# CAN.net
KiCad netlist of a schematic drawn in Altium Designer
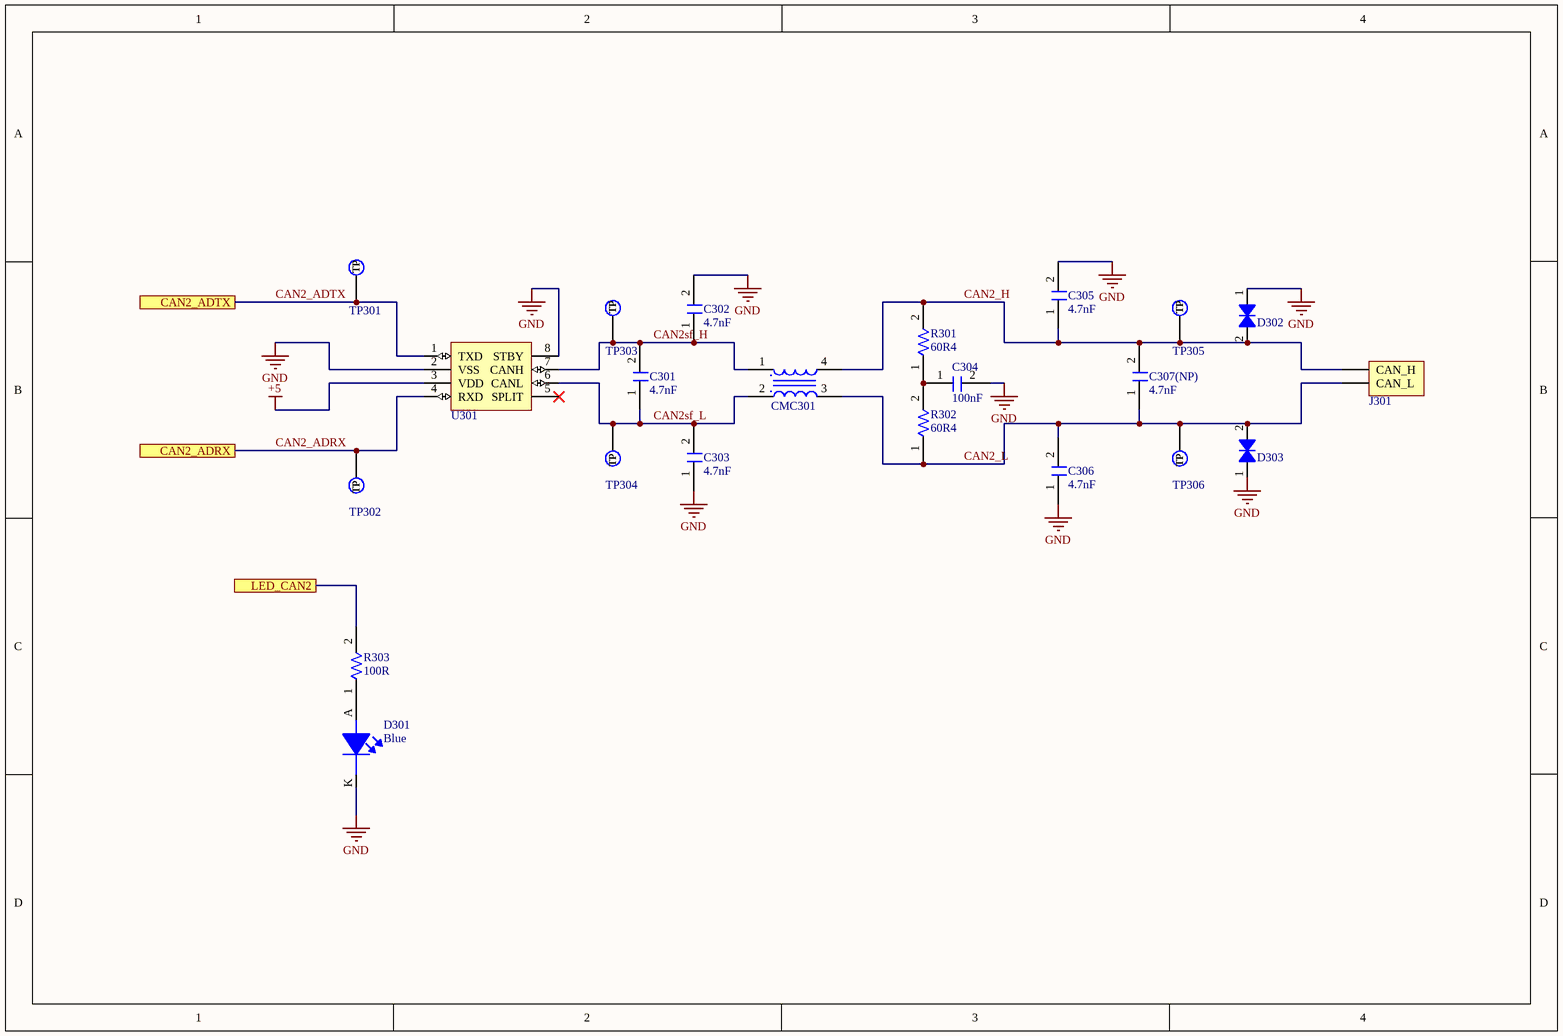
[diagram p0: CAN.SchDoc]

(export (version "E")
  (design (tool "Eeschema 10.0.6"))
  (components
    (comp (ref "C301")
      (value "885012208025")
      (footprint "C1206FNPC-RW")
      (description "Cap, 4700PF, 16V, 10%, X7R, 1206")
      (fields
        (field (name "MANUFACTURER") "Wurth Electronics")
        (field (name "TOLERANCE") "10%")
        (field (name "CAPACITANCE") "4.7nF")
      )
      (libsource (lib "Passives") (part "C4.7n-16V-1206FNPC-X7R"))
    )
    (comp (ref "C302")
      (value "885012208025")
      (footprint "C1206FNPC-RW")
      (description "Cap, 4700PF, 16V, 10%, X7R, 1206")
      (fields
        (field (name "MANUFACTURER") "Wurth Electronics")
        (field (name "TOLERANCE") "10%")
        (field (name "CAPACITANCE") "4.7nF")
      )
      (libsource (lib "Passives") (part "C4.7n-16V-1206FNPC-X7R"))
    )
    (comp (ref "C303")
      (value "885012208025")
      (footprint "C1206FNPC-RW")
      (description "Cap, 4700PF, 16V, 10%, X7R, 1206")
      (fields
        (field (name "MANUFACTURER") "Wurth Electronics")
        (field (name "TOLERANCE") "10%")
        (field (name "CAPACITANCE") "4.7nF")
      )
      (libsource (lib "Passives") (part "C4.7n-16V-1206FNPC-X7R"))
    )
    (comp (ref "C304")
      (value "885012208009")
      (footprint "C1206FNPC-RW")
      (description "Cap, 0.1ΜF, 10V, 10%, X7R, 1206")
      (fields (field (name "TOLERANCE") "10%") (field (name "CAPACITANCE") "100nF"))
      (libsource (lib "Passives") (part "C100n-10V-1206FNPC-X7R"))
    )
    (comp (ref "C305")
      (value "885012208025")
      (footprint "C1206FNPC-RW")
      (description "Cap, 4700PF, 16V, 10%, X7R, 1206")
      (fields
        (field (name "MANUFACTURER") "Wurth Electronics")
        (field (name "TOLERANCE") "10%")
        (field (name "CAPACITANCE") "4.7nF")
      )
      (libsource (lib "Passives") (part "C4.7n-16V-1206FNPC-X7R"))
    )
    (comp (ref "C306")
      (value "885012208025")
      (footprint "C1206FNPC-RW")
      (description "Cap, 4700PF, 16V, 10%, X7R, 1206")
      (fields
        (field (name "MANUFACTURER") "Wurth Electronics")
        (field (name "TOLERANCE") "10%")
        (field (name "CAPACITANCE") "4.7nF")
      )
      (libsource (lib "Passives") (part "C4.7n-16V-1206FNPC-X7R"))
    )
    (comp (ref "C307(NP)")
      (value "885012208025")
      (footprint "C1206FNPC-RW")
      (description "Cap, 4700PF, 16V, 10%, X7R, 1206")
      (fields
        (field (name "MANUFACTURER") "Wurth Electronics")
        (field (name "TOLERANCE") "10%")
        (field (name "CAPACITANCE") "4.7nF")
      )
      (libsource (lib "Passives") (part "C4.7n-16V-1206FNPC-X7R"))
    )
    (comp (ref "CMC301")
      (value "744226")
      (footprint "CMC_10u_1.6A")
      (description "Common Mode Chokes Dual 10uH 920Ohm 1kHz 1.6A 80mOhm DCR SMD T/R")
      (fields (field (name "MANUFACTURER") "Wurth Electronics") (field (name "TOLERANCE") "30%"))
      (libsource (lib "Filter components") (part "CMC_10u_1.6A"))
    )
    (comp (ref "D301")
      (value "150120BS75000")
      (footprint "LED_1206_WE")
      (description "Led, Blue, 470 Nm, 3.2 V, 30 Ma, 145 Mcd Rohs Compliant: Yes")
      (fields (field (name "MANUFACTURER") "Wurth Electronics") (field (name "COLOR") "Blue"))
      (libsource (lib "Semiconductor") (part "LEDBS-1206-145"))
    )
    (comp (ref "D302")
      (value "824501600")
      (footprint "DTVS-DO-214AC")
      (description "TVS diode [Würth Elektronik] 824501600 TVS diode")
      (fields (field (name "MANUFACTURER") "Wurth Electronics"))
      (libsource (lib "Filter components") (part "DTVS-6V-DO-214AC"))
    )
    (comp (ref "D303")
      (value "824501600")
      (footprint "DTVS-DO-214AC")
      (description "TVS diode [Würth Elektronik] 824501600 TVS diode")
      (fields (field (name "MANUFACTURER") "Wurth Electronics"))
      (libsource (lib "Filter components") (part "DTVS-6V-DO-214AC"))
    )
    (comp (ref "J301")
      (value "430450200")
      (footprint "J_CAN")
      (description "Header 2 Row Right-Angle Snap-In Lock 2Pin Tin Plate SMT/Glow Wire Compatible")
      (fields (field (name "MANUFACTURER") "Molex"))
      (libsource (lib "Electromechanical") (part "J_CAN"))
    )
    (comp (ref "R301")
      (value "60R4")
      (footprint "R1206FTK-W")
      (description "Res Precision Thin Film 60.4Ohm 0.1% 400mW 10ppm/°C 2-Pin 1206 SMD T/R")
      (fields
        (field (name "MANUFACTURER") "TE Connectivity Holsworthy")
        (field (name "MANUFACTURER PART NUMBER") "RQ73C2B60R4BTDF")
      )
      (libsource (lib "Passives") (part "R60-1206FTN"))
    )
    (comp (ref "R302")
      (value "60R4")
      (footprint "R1206FTK-W")
      (description "Res Precision Thin Film 60.4Ohm 0.1% 400mW 10ppm/°C 2-Pin 1206 SMD T/R")
      (fields
        (field (name "MANUFACTURER") "TE Connectivity Holsworthy")
        (field (name "MANUFACTURER PART NUMBER") "RQ73C2B60R4BTDF")
      )
      (libsource (lib "Passives") (part "R60-1206FTN"))
    )
    (comp (ref "R303")
      (value "CRG1206F100R")
      (footprint "R1206FTK-W")
      (description "Res Thick Film 1206 100 Ohm 1% 0.25W(1/4W) ±200ppm/C Pad SMD T/R")
      (fields
        (field (name "MANUFACTURER") "TE Connectivity")
        (field (name "TOLERANCE") "1%")
        (field (name "RESISTANCE") "100R")
      )
      (libsource (lib "Passives") (part "R100-1206FTK"))
    )
    (comp (ref "TP301")
      (value "TestPoint")
      (footprint "TestPoint")
      (description "Test Point 1x1 mm")
      (libsource (lib "e-Tech_Racing") (part "TestPoint"))
    )
    (comp (ref "TP302")
      (value "TestPoint")
      (footprint "TestPoint")
      (description "Test Point 1x1 mm")
      (libsource (lib "e-Tech_Racing") (part "TestPoint"))
    )
    (comp (ref "TP303")
      (value "TestPoint")
      (footprint "TestPoint")
      (description "Test Point 1x1 mm")
      (libsource (lib "e-Tech_Racing") (part "TestPoint"))
    )
    (comp (ref "TP304")
      (value "TestPoint")
      (footprint "TestPoint")
      (description "Test Point 1x1 mm")
      (libsource (lib "e-Tech_Racing") (part "TestPoint"))
    )
    (comp (ref "TP305")
      (value "TestPoint")
      (footprint "TestPoint")
      (description "Test Point 1x1 mm")
      (libsource (lib "e-Tech_Racing") (part "TestPoint"))
    )
    (comp (ref "TP306")
      (value "TestPoint")
      (footprint "TestPoint")
      (description "Test Point 1x1 mm")
      (libsource (lib "e-Tech_Racing") (part "TestPoint"))
    )
    (comp (ref "U301")
      (value "MCP2561-H/SN")
      (footprint "Transceiver_CAN")
      (description "CAN Transceiver, 4.5 to 5.5V, 70mA, -40 to 150C, SOIC-8, RoHS")
      (fields (field (name "MANUFACTURER") "Digi-Key") (field (name "MANUFACTURER PART") "Microchip"))
      (libsource (lib "Integrated circuits") (part "Transceiver_CAN"))
    )
  )
  (nets
    (net (code "1") (name "+5") (class "Default")
      (node (ref "U301") (pin "3") (pinfunction "VDD_3") (pintype "power_in"))
    )
    (net (code "2") (name "/CAN2_ADRX") (class "Default")
      (node (ref "TP302") (pin "1") (pinfunction "TP_1") (pintype "passive"))
      (node (ref "U301") (pin "4") (pinfunction "RXD_4") (pintype "bidirectional"))
    )
    (net (code "3") (name "/CAN2_ADTX") (class "Default")
      (node (ref "TP301") (pin "1") (pinfunction "TP_1") (pintype "passive"))
      (node (ref "U301") (pin "1") (pinfunction "TXD_1") (pintype "bidirectional"))
    )
    (net (code "4") (name "/CAN2_H") (class "Default")
      (node (ref "C305") (pin "1") (pinfunction "1_1") (pintype "passive"))
      (node (ref "C307(NP)") (pin "2") (pinfunction "2_2") (pintype "passive"))
      (node (ref "CMC301") (pin "4") (pinfunction "4_OUT_4") (pintype "passive"))
      (node (ref "D302") (pin "2") (pinfunction "2_2") (pintype "passive"))
      (node (ref "J301") (pin "1") (pinfunction "CAN_H_1") (pintype "passive"))
      (node (ref "R301") (pin "2") (pinfunction "2_2") (pintype "passive"))
      (node (ref "TP305") (pin "1") (pinfunction "TP_1") (pintype "passive"))
    )
    (net (code "5") (name "/CAN2_L") (class "Default")
      (node (ref "C306") (pin "2") (pinfunction "2_2") (pintype "passive"))
      (node (ref "C307(NP)") (pin "1") (pinfunction "1_1") (pintype "passive"))
      (node (ref "CMC301") (pin "3") (pinfunction "3_OUT_3") (pintype "passive"))
      (node (ref "D303") (pin "2") (pinfunction "2_2") (pintype "passive"))
      (node (ref "J301") (pin "2") (pinfunction "CAN_L_2") (pintype "passive"))
      (node (ref "R302") (pin "1") (pinfunction "1_1") (pintype "passive"))
      (node (ref "TP306") (pin "1") (pinfunction "TP_1") (pintype "passive"))
    )
    (net (code "6") (name "/CAN2sf_H") (class "Default")
      (node (ref "C301") (pin "2") (pinfunction "2_2") (pintype "passive"))
      (node (ref "C302") (pin "1") (pinfunction "1_1") (pintype "passive"))
      (node (ref "CMC301") (pin "1") (pinfunction "1_IN_1") (pintype "passive"))
      (node (ref "TP303") (pin "1") (pinfunction "TP_1") (pintype "passive"))
      (node (ref "U301") (pin "7") (pinfunction "CANH_7") (pintype "bidirectional"))
    )
    (net (code "7") (name "/CAN2sf_L") (class "Default")
      (node (ref "C301") (pin "1") (pinfunction "1_1") (pintype "passive"))
      (node (ref "C303") (pin "2") (pinfunction "2_2") (pintype "passive"))
      (node (ref "CMC301") (pin "2") (pinfunction "2_IN_2") (pintype "passive"))
      (node (ref "TP304") (pin "1") (pinfunction "TP_1") (pintype "passive"))
      (node (ref "U301") (pin "6") (pinfunction "CANL_6") (pintype "bidirectional"))
    )
    (net (code "8") (name "/LED_CAN2") (class "Default")
      (node (ref "R303") (pin "2") (pinfunction "2_2") (pintype "passive"))
    )
    (net (code "9") (name "GND") (class "Default")
      (node (ref "C302") (pin "2") (pinfunction "2_2") (pintype "passive"))
      (node (ref "C303") (pin "1") (pinfunction "1_1") (pintype "passive"))
      (node (ref "C304") (pin "2") (pinfunction "2_2") (pintype "passive"))
      (node (ref "C305") (pin "2") (pinfunction "2_2") (pintype "passive"))
      (node (ref "C306") (pin "1") (pinfunction "1_1") (pintype "passive"))
      (node (ref "D301") (pin "K") (pinfunction "K_K") (pintype "passive"))
      (node (ref "D302") (pin "1") (pinfunction "1_1") (pintype "passive"))
      (node (ref "D303") (pin "1") (pinfunction "1_1") (pintype "passive"))
      (node (ref "U301") (pin "2") (pinfunction "VSS_2") (pintype "power_in"))
      (node (ref "U301") (pin "8") (pinfunction "STBY_8") (pintype "passive"))
    )
    (net (code "10") (name "Net-(C304-Pad1)") (class "Default")
      (node (ref "C304") (pin "1") (pinfunction "1_1") (pintype "passive"))
      (node (ref "R301") (pin "1") (pinfunction "1_1") (pintype "passive"))
      (node (ref "R302") (pin "2") (pinfunction "2_2") (pintype "passive"))
    )
    (net (code "11") (name "Net-(D301-PadA)") (class "Default")
      (node (ref "D301") (pin "A") (pinfunction "A_A") (pintype "passive"))
      (node (ref "R303") (pin "1") (pinfunction "1_1") (pintype "passive"))
    )
    (net (code "12") (name "unconnected-(U301-SPLIT-Pad5)") (class "Default")
      (node (ref "U301") (pin "5") (pinfunction "SPLIT_5") (pintype "passive+no_connect"))
    )
  )
)
